# 20210915_EleksTube_IPS_midextend.net
KiCad netlist of a schematic drawn in Altium Designer
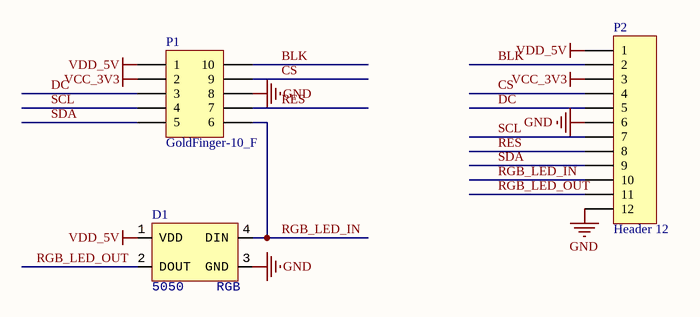
[diagram p0: 20210915_EleksTube_IPS_midextend.SchDoc]

(export (version "E")
  (design (tool "Eeschema 10.0.6"))
  (components
    (comp (ref "D1")
      (value "RGB")
      (footprint "LED_5050_WS2812B")
      (description "LED")
      (fields (field (name "TYPE") "5050"))
      (libsource (lib "KitSprout") (part "LED_5050_WS2812B"))
    )
    (comp (ref "P1")
      (value "GoldFinger-10_F")
      (footprint "GoldFinger-10_F")
      (description "Header, 5-Pin, Dual row")
      (fields (field (name "PUBLISHER") "Altium Limited"))
      (libsource (lib "20210226_EleksTube_IPS_main") (part "GoldFinger-10_F"))
    )
    (comp (ref "P2")
      (value "Header 12")
      (footprint "SIP12-1.27")
      (description "Header, 12-Pin")
      (fields (field (name "PUBLISHER") "Altium Limited"))
      (libsource (lib "Miscellaneous Connectors") (part "Header 12"))
    )
  )
  (nets
    (net (code "1") (name "/BLK") (class "Default")
      (node (ref "P1") (pin "10") (pinfunction "10_10") (pintype "passive"))
      (node (ref "P2") (pin "2") (pinfunction "2_2") (pintype "passive"))
    )
    (net (code "2") (name "/CS") (class "Default")
      (node (ref "P1") (pin "9") (pinfunction "9_9") (pintype "passive"))
      (node (ref "P2") (pin "4") (pinfunction "4_4") (pintype "passive"))
    )
    (net (code "3") (name "/DC") (class "Default")
      (node (ref "P1") (pin "3") (pinfunction "3_3") (pintype "passive"))
      (node (ref "P2") (pin "5") (pinfunction "5_5") (pintype "passive"))
    )
    (net (code "4") (name "/RES") (class "Default")
      (node (ref "P1") (pin "7") (pinfunction "7_7") (pintype "passive"))
      (node (ref "P2") (pin "8") (pinfunction "8_8") (pintype "passive"))
    )
    (net (code "5") (name "/RGB_LED_IN") (class "Default")
      (node (ref "D1") (pin "4") (pinfunction "DIN_4") (pintype "passive"))
      (node (ref "P1") (pin "6") (pinfunction "6_6") (pintype "passive"))
      (node (ref "P2") (pin "10") (pinfunction "10_10") (pintype "passive"))
    )
    (net (code "6") (name "/RGB_LED_OUT") (class "Default")
      (node (ref "D1") (pin "2") (pinfunction "DOUT_2") (pintype "passive"))
      (node (ref "P2") (pin "11") (pinfunction "11_11") (pintype "passive"))
    )
    (net (code "7") (name "/SCL") (class "Default")
      (node (ref "P1") (pin "4") (pinfunction "4_4") (pintype "passive"))
      (node (ref "P2") (pin "7") (pinfunction "7_7") (pintype "passive"))
    )
    (net (code "8") (name "/SDA") (class "Default")
      (node (ref "P1") (pin "5") (pinfunction "5_5") (pintype "passive"))
      (node (ref "P2") (pin "9") (pinfunction "9_9") (pintype "passive"))
    )
    (net (code "9") (name "GND") (class "Default")
      (node (ref "D1") (pin "3") (pinfunction "GND_3") (pintype "passive"))
      (node (ref "P1") (pin "8") (pinfunction "8_8") (pintype "passive"))
      (node (ref "P2") (pin "12") (pinfunction "12_12") (pintype "passive"))
      (node (ref "P2") (pin "6") (pinfunction "6_6") (pintype "passive"))
    )
    (net (code "10") (name "VCC_3V3") (class "Default")
      (node (ref "P1") (pin "2") (pinfunction "2_2") (pintype "passive"))
      (node (ref "P2") (pin "3") (pinfunction "3_3") (pintype "passive"))
    )
    (net (code "11") (name "VDD_5V") (class "Default")
      (node (ref "D1") (pin "1") (pinfunction "VDD_1") (pintype "passive"))
      (node (ref "P1") (pin "1") (pinfunction "1_1") (pintype "passive"))
      (node (ref "P2") (pin "1") (pinfunction "1_1") (pintype "passive"))
    )
  )
)
